# output.net
KiCad netlist of a schematic drawn in Altium Designer
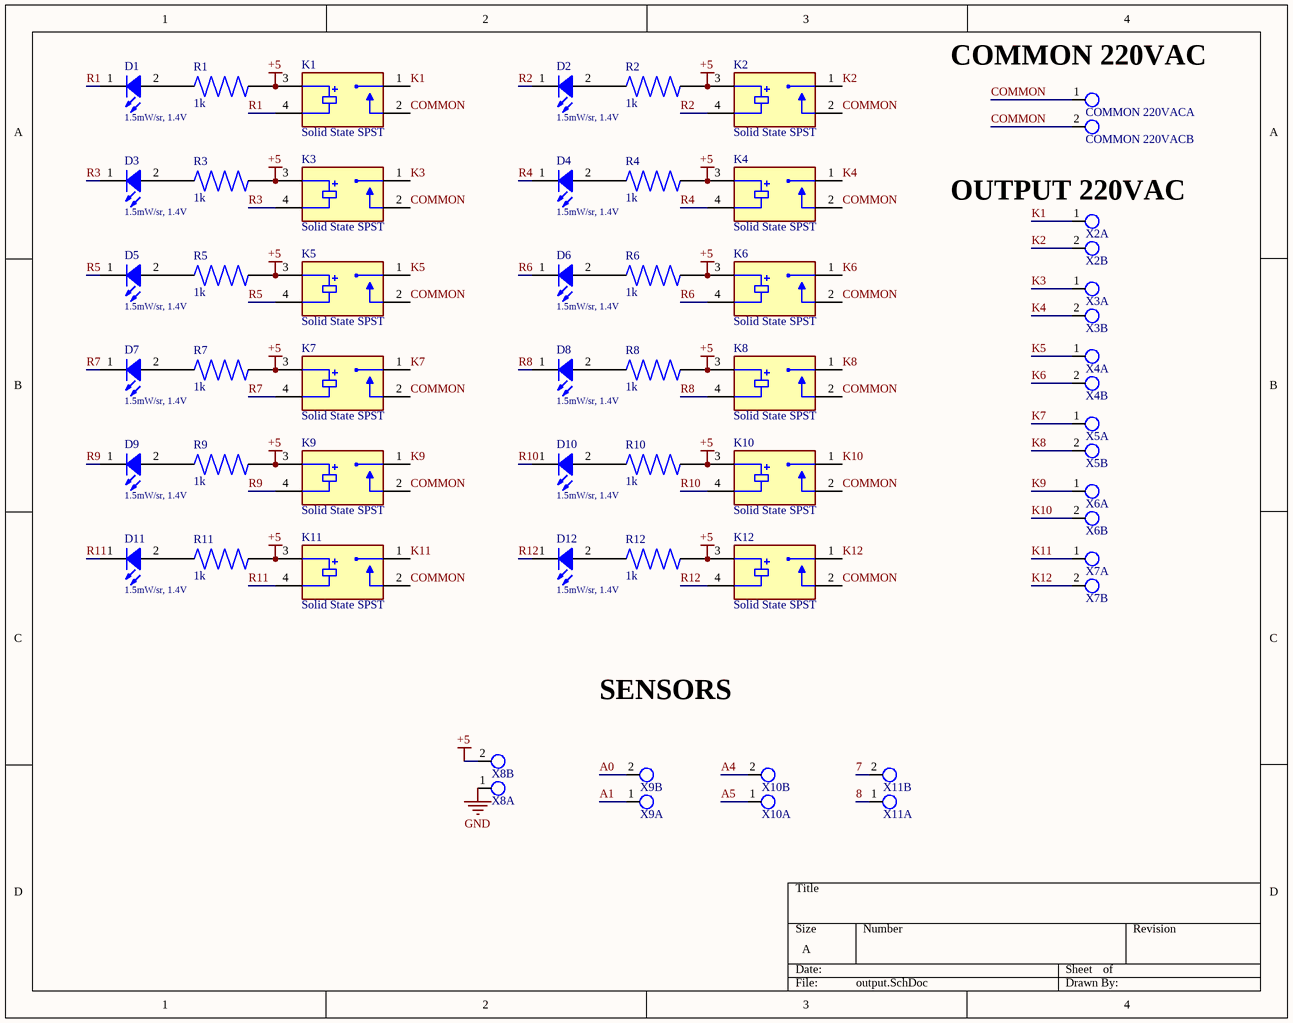
[diagram p0: output.SchDoc]

(export (version "E")
  (design (tool "Eeschema 10.0.6"))
  (components
    (comp (ref "COMMON 220VAC")
      (value "AK300/2")
      (footprint "AK300/2")
      (fields (field (name "MP") "AK300/3") (field (name "MF") "Altech"))
      (libsource (lib "") (part "AK300/2_2"))
    )
    (comp (ref "D1")
      (value "1.5mW/sr, 1.4V")
      (footprint "0805_L2W1.3H0.8")
      (description "WL-SICW SMT Chip LED Infrared Waterclear, size 0805, 1.5mW/sr, 1.4V")
      (fields
        (field (name "MANUFACTURER PART NUMBER") "15408085BA400")
        (field (name "MANUFACTURER") "Wurth Elektronik")
      )
      (libsource (lib "input") (part "0805 Led"))
    )
    (comp (ref "D2")
      (value "1.5mW/sr, 1.4V")
      (footprint "0805_L2W1.3H0.8")
      (description "WL-SICW SMT Chip LED Infrared Waterclear, size 0805, 1.5mW/sr, 1.4V")
      (fields
        (field (name "MANUFACTURER PART NUMBER") "15408085BA400")
        (field (name "MANUFACTURER") "Wurth Elektronik")
      )
      (libsource (lib "input") (part "0805 Led"))
    )
    (comp (ref "D3")
      (value "1.5mW/sr, 1.4V")
      (footprint "0805_L2W1.3H0.8")
      (description "WL-SICW SMT Chip LED Infrared Waterclear, size 0805, 1.5mW/sr, 1.4V")
      (fields
        (field (name "MANUFACTURER PART NUMBER") "15408085BA400")
        (field (name "MANUFACTURER") "Wurth Elektronik")
      )
      (libsource (lib "input") (part "0805 Led"))
    )
    (comp (ref "D4")
      (value "1.5mW/sr, 1.4V")
      (footprint "0805_L2W1.3H0.8")
      (description "WL-SICW SMT Chip LED Infrared Waterclear, size 0805, 1.5mW/sr, 1.4V")
      (fields
        (field (name "MANUFACTURER PART NUMBER") "15408085BA400")
        (field (name "MANUFACTURER") "Wurth Elektronik")
      )
      (libsource (lib "input") (part "0805 Led"))
    )
    (comp (ref "D5")
      (value "1.5mW/sr, 1.4V")
      (footprint "0805_L2W1.3H0.8")
      (description "WL-SICW SMT Chip LED Infrared Waterclear, size 0805, 1.5mW/sr, 1.4V")
      (fields
        (field (name "MANUFACTURER PART NUMBER") "15408085BA400")
        (field (name "MANUFACTURER") "Wurth Elektronik")
      )
      (libsource (lib "input") (part "0805 Led"))
    )
    (comp (ref "D6")
      (value "1.5mW/sr, 1.4V")
      (footprint "0805_L2W1.3H0.8")
      (description "WL-SICW SMT Chip LED Infrared Waterclear, size 0805, 1.5mW/sr, 1.4V")
      (fields
        (field (name "MANUFACTURER PART NUMBER") "15408085BA400")
        (field (name "MANUFACTURER") "Wurth Elektronik")
      )
      (libsource (lib "input") (part "0805 Led"))
    )
    (comp (ref "D7")
      (value "1.5mW/sr, 1.4V")
      (footprint "0805_L2W1.3H0.8")
      (description "WL-SICW SMT Chip LED Infrared Waterclear, size 0805, 1.5mW/sr, 1.4V")
      (fields
        (field (name "MANUFACTURER PART NUMBER") "15408085BA400")
        (field (name "MANUFACTURER") "Wurth Elektronik")
      )
      (libsource (lib "input") (part "0805 Led"))
    )
    (comp (ref "D8")
      (value "1.5mW/sr, 1.4V")
      (footprint "0805_L2W1.3H0.8")
      (description "WL-SICW SMT Chip LED Infrared Waterclear, size 0805, 1.5mW/sr, 1.4V")
      (fields
        (field (name "MANUFACTURER PART NUMBER") "15408085BA400")
        (field (name "MANUFACTURER") "Wurth Elektronik")
      )
      (libsource (lib "input") (part "0805 Led"))
    )
    (comp (ref "D9")
      (value "1.5mW/sr, 1.4V")
      (footprint "0805_L2W1.3H0.8")
      (description "WL-SICW SMT Chip LED Infrared Waterclear, size 0805, 1.5mW/sr, 1.4V")
      (fields
        (field (name "MANUFACTURER PART NUMBER") "15408085BA400")
        (field (name "MANUFACTURER") "Wurth Elektronik")
      )
      (libsource (lib "input") (part "0805 Led"))
    )
    (comp (ref "D10")
      (value "1.5mW/sr, 1.4V")
      (footprint "0805_L2W1.3H0.8")
      (description "WL-SICW SMT Chip LED Infrared Waterclear, size 0805, 1.5mW/sr, 1.4V")
      (fields
        (field (name "MANUFACTURER PART NUMBER") "15408085BA400")
        (field (name "MANUFACTURER") "Wurth Elektronik")
      )
      (libsource (lib "input") (part "0805 Led"))
    )
    (comp (ref "D11")
      (value "1.5mW/sr, 1.4V")
      (footprint "0805_L2W1.3H0.8")
      (description "WL-SICW SMT Chip LED Infrared Waterclear, size 0805, 1.5mW/sr, 1.4V")
      (fields
        (field (name "MANUFACTURER PART NUMBER") "15408085BA400")
        (field (name "MANUFACTURER") "Wurth Elektronik")
      )
      (libsource (lib "input") (part "0805 Led"))
    )
    (comp (ref "D12")
      (value "1.5mW/sr, 1.4V")
      (footprint "0805_L2W1.3H0.8")
      (description "WL-SICW SMT Chip LED Infrared Waterclear, size 0805, 1.5mW/sr, 1.4V")
      (fields
        (field (name "MANUFACTURER PART NUMBER") "15408085BA400")
        (field (name "MANUFACTURER") "Wurth Elektronik")
      )
      (libsource (lib "input") (part "0805 Led"))
    )
    (comp (ref "K1")
      (value "Solid State SPST")
      (footprint "Solid State SPST")
      (description "Solid State SPST-NO (1 Form A) 4-SIP")
      (fields (field (name "MF") "Omron Automation") (field (name "MP") "G3MB-202P DC5"))
      (libsource (lib "control") (part "Solid State SPST"))
    )
    (comp (ref "K2")
      (value "Solid State SPST")
      (footprint "Solid State SPST")
      (description "Solid State SPST-NO (1 Form A) 4-SIP")
      (fields (field (name "MF") "Omron Automation") (field (name "MP") "G3MB-202P DC5"))
      (libsource (lib "control") (part "Solid State SPST"))
    )
    (comp (ref "K3")
      (value "Solid State SPST")
      (footprint "Solid State SPST")
      (description "Solid State SPST-NO (1 Form A) 4-SIP")
      (fields (field (name "MF") "Omron Automation") (field (name "MP") "G3MB-202P DC5"))
      (libsource (lib "control") (part "Solid State SPST"))
    )
    (comp (ref "K4")
      (value "Solid State SPST")
      (footprint "Solid State SPST")
      (description "Solid State SPST-NO (1 Form A) 4-SIP")
      (fields (field (name "MF") "Omron Automation") (field (name "MP") "G3MB-202P DC5"))
      (libsource (lib "control") (part "Solid State SPST"))
    )
    (comp (ref "K5")
      (value "Solid State SPST")
      (footprint "Solid State SPST")
      (description "Solid State SPST-NO (1 Form A) 4-SIP")
      (fields (field (name "MF") "Omron Automation") (field (name "MP") "G3MB-202P DC5"))
      (libsource (lib "control") (part "Solid State SPST"))
    )
    (comp (ref "K6")
      (value "Solid State SPST")
      (footprint "Solid State SPST")
      (description "Solid State SPST-NO (1 Form A) 4-SIP")
      (fields (field (name "MF") "Omron Automation") (field (name "MP") "G3MB-202P DC5"))
      (libsource (lib "control") (part "Solid State SPST"))
    )
    (comp (ref "K7")
      (value "Solid State SPST")
      (footprint "Solid State SPST")
      (description "Solid State SPST-NO (1 Form A) 4-SIP")
      (fields (field (name "MF") "Omron Automation") (field (name "MP") "G3MB-202P DC5"))
      (libsource (lib "control") (part "Solid State SPST"))
    )
    (comp (ref "K8")
      (value "Solid State SPST")
      (footprint "Solid State SPST")
      (description "Solid State SPST-NO (1 Form A) 4-SIP")
      (fields (field (name "MF") "Omron Automation") (field (name "MP") "G3MB-202P DC5"))
      (libsource (lib "control") (part "Solid State SPST"))
    )
    (comp (ref "K9")
      (value "Solid State SPST")
      (footprint "Solid State SPST")
      (description "Solid State SPST-NO (1 Form A) 4-SIP")
      (fields (field (name "MF") "Omron Automation") (field (name "MP") "G3MB-202P DC5"))
      (libsource (lib "control") (part "Solid State SPST"))
    )
    (comp (ref "K10")
      (value "Solid State SPST")
      (footprint "Solid State SPST")
      (description "Solid State SPST-NO (1 Form A) 4-SIP")
      (fields (field (name "MF") "Omron Automation") (field (name "MP") "G3MB-202P DC5"))
      (libsource (lib "control") (part "Solid State SPST"))
    )
    (comp (ref "K11")
      (value "Solid State SPST")
      (footprint "Solid State SPST")
      (description "Solid State SPST-NO (1 Form A) 4-SIP")
      (fields (field (name "MF") "Omron Automation") (field (name "MP") "G3MB-202P DC5"))
      (libsource (lib "control") (part "Solid State SPST"))
    )
    (comp (ref "K12")
      (value "Solid State SPST")
      (footprint "Solid State SPST")
      (description "Solid State SPST-NO (1 Form A) 4-SIP")
      (fields (field (name "MF") "Omron Automation") (field (name "MP") "G3MB-202P DC5"))
      (libsource (lib "control") (part "Solid State SPST"))
    )
    (comp (ref "R1")
      (value "1k")
      (footprint "1206")
      (description "Res 1206 10 Ohm 5% 1/8W Â±500ppm/Â°C Molded SMD SMD T/R")
      (fields (field (name "TOLERANCE") "5%") (field (name "MP") "FCR1206J10R"))
      (libsource (lib "input") (part "1206 Res"))
    )
    (comp (ref "R2")
      (value "1k")
      (footprint "1206")
      (description "Res 1206 10 Ohm 5% 1/8W Â±500ppm/Â°C Molded SMD SMD T/R")
      (fields (field (name "TOLERANCE") "5%") (field (name "MP") "FCR1206J10R"))
      (libsource (lib "input") (part "1206 Res"))
    )
    (comp (ref "R3")
      (value "1k")
      (footprint "1206")
      (description "Res 1206 10 Ohm 5% 1/8W Â±500ppm/Â°C Molded SMD SMD T/R")
      (fields (field (name "TOLERANCE") "5%") (field (name "MP") "FCR1206J10R"))
      (libsource (lib "input") (part "1206 Res"))
    )
    (comp (ref "R4")
      (value "1k")
      (footprint "1206")
      (description "Res 1206 10 Ohm 5% 1/8W Â±500ppm/Â°C Molded SMD SMD T/R")
      (fields (field (name "TOLERANCE") "5%") (field (name "MP") "FCR1206J10R"))
      (libsource (lib "input") (part "1206 Res"))
    )
    (comp (ref "R5")
      (value "1k")
      (footprint "1206")
      (description "Res 1206 10 Ohm 5% 1/8W Â±500ppm/Â°C Molded SMD SMD T/R")
      (fields (field (name "TOLERANCE") "5%") (field (name "MP") "FCR1206J10R"))
      (libsource (lib "input") (part "1206 Res"))
    )
    (comp (ref "R6")
      (value "1k")
      (footprint "1206")
      (description "Res 1206 10 Ohm 5% 1/8W Â±500ppm/Â°C Molded SMD SMD T/R")
      (fields (field (name "TOLERANCE") "5%") (field (name "MP") "FCR1206J10R"))
      (libsource (lib "input") (part "1206 Res"))
    )
    (comp (ref "R7")
      (value "1k")
      (footprint "1206")
      (description "Res 1206 10 Ohm 5% 1/8W Â±500ppm/Â°C Molded SMD SMD T/R")
      (fields (field (name "TOLERANCE") "5%") (field (name "MP") "FCR1206J10R"))
      (libsource (lib "input") (part "1206 Res"))
    )
    (comp (ref "R8")
      (value "1k")
      (footprint "1206")
      (description "Res 1206 10 Ohm 5% 1/8W Â±500ppm/Â°C Molded SMD SMD T/R")
      (fields (field (name "TOLERANCE") "5%") (field (name "MP") "FCR1206J10R"))
      (libsource (lib "input") (part "1206 Res"))
    )
    (comp (ref "R9")
      (value "1k")
      (footprint "1206")
      (description "Res 1206 10 Ohm 5% 1/8W Â±500ppm/Â°C Molded SMD SMD T/R")
      (fields (field (name "TOLERANCE") "5%") (field (name "MP") "FCR1206J10R"))
      (libsource (lib "input") (part "1206 Res"))
    )
    (comp (ref "R10")
      (value "1k")
      (footprint "1206")
      (description "Res 1206 10 Ohm 5% 1/8W Â±500ppm/Â°C Molded SMD SMD T/R")
      (fields (field (name "TOLERANCE") "5%") (field (name "MP") "FCR1206J10R"))
      (libsource (lib "input") (part "1206 Res"))
    )
    (comp (ref "R11")
      (value "1k")
      (footprint "1206")
      (description "Res 1206 10 Ohm 5% 1/8W Â±500ppm/Â°C Molded SMD SMD T/R")
      (fields (field (name "TOLERANCE") "5%") (field (name "MP") "FCR1206J10R"))
      (libsource (lib "input") (part "1206 Res"))
    )
    (comp (ref "R12")
      (value "1k")
      (footprint "1206")
      (description "Res 1206 10 Ohm 5% 1/8W Â±500ppm/Â°C Molded SMD SMD T/R")
      (fields (field (name "TOLERANCE") "5%") (field (name "MP") "FCR1206J10R"))
      (libsource (lib "input") (part "1206 Res"))
    )
    (comp (ref "X2")
      (value "AK300/2")
      (footprint "AK300/2")
      (fields (field (name "MP") "AK300/3") (field (name "MF") "Altech"))
      (libsource (lib "input") (part "AK300/2"))
    )
    (comp (ref "X3")
      (value "AK300/2")
      (footprint "AK300/2")
      (fields (field (name "MP") "AK300/3") (field (name "MF") "Altech"))
      (libsource (lib "input") (part "AK300/2"))
    )
    (comp (ref "X4")
      (value "AK300/2")
      (footprint "AK300/2")
      (fields (field (name "MP") "AK300/3") (field (name "MF") "Altech"))
      (libsource (lib "input") (part "AK300/2"))
    )
    (comp (ref "X5")
      (value "AK300/2")
      (footprint "AK300/2")
      (fields (field (name "MP") "AK300/3") (field (name "MF") "Altech"))
      (libsource (lib "input") (part "AK300/2"))
    )
    (comp (ref "X6")
      (value "AK300/2")
      (footprint "AK300/2")
      (fields (field (name "MP") "AK300/3") (field (name "MF") "Altech"))
      (libsource (lib "input") (part "AK300/2"))
    )
    (comp (ref "X7")
      (value "AK300/2")
      (footprint "AK300/2")
      (fields (field (name "MP") "AK300/3") (field (name "MF") "Altech"))
      (libsource (lib "input") (part "AK300/2"))
    )
    (comp (ref "X8")
      (value "AK300/2")
      (footprint "AK300/2")
      (fields (field (name "MP") "AK300/3") (field (name "MF") "Altech"))
      (libsource (lib "") (part "AK300/2_2"))
    )
    (comp (ref "X9")
      (value "AK300/2")
      (footprint "AK300/2")
      (fields (field (name "MP") "AK300/3") (field (name "MF") "Altech"))
      (libsource (lib "") (part "AK300/2_1"))
    )
    (comp (ref "X10")
      (value "AK300/2")
      (footprint "AK300/2")
      (fields (field (name "MP") "AK300/3") (field (name "MF") "Altech"))
      (libsource (lib "") (part "AK300/2_1"))
    )
    (comp (ref "X11")
      (value "AK300/2")
      (footprint "AK300/2")
      (fields (field (name "MP") "AK300/3") (field (name "MF") "Altech"))
      (libsource (lib "") (part "AK300/2_2"))
    )
  )
  (nets
    (net (code "1") (name "+5") (class "Default")
      (node (ref "K1") (pin "3") (pinfunction "3_3") (pintype "passive"))
      (node (ref "K10") (pin "3") (pinfunction "3_3") (pintype "passive"))
      (node (ref "K11") (pin "3") (pinfunction "3_3") (pintype "passive"))
      (node (ref "K12") (pin "3") (pinfunction "3_3") (pintype "passive"))
      (node (ref "K2") (pin "3") (pinfunction "3_3") (pintype "passive"))
      (node (ref "K3") (pin "3") (pinfunction "3_3") (pintype "passive"))
      (node (ref "K4") (pin "3") (pinfunction "3_3") (pintype "passive"))
      (node (ref "K5") (pin "3") (pinfunction "3_3") (pintype "passive"))
      (node (ref "K6") (pin "3") (pinfunction "3_3") (pintype "passive"))
      (node (ref "K7") (pin "3") (pinfunction "3_3") (pintype "passive"))
      (node (ref "K8") (pin "3") (pinfunction "3_3") (pintype "passive"))
      (node (ref "K9") (pin "3") (pinfunction "3_3") (pintype "passive"))
      (node (ref "R1") (pin "2") (pinfunction "2_2") (pintype "passive"))
      (node (ref "R10") (pin "2") (pinfunction "2_2") (pintype "passive"))
      (node (ref "R11") (pin "2") (pinfunction "2_2") (pintype "passive"))
      (node (ref "R12") (pin "2") (pinfunction "2_2") (pintype "passive"))
      (node (ref "R2") (pin "2") (pinfunction "2_2") (pintype "passive"))
      (node (ref "R3") (pin "2") (pinfunction "2_2") (pintype "passive"))
      (node (ref "R4") (pin "2") (pinfunction "2_2") (pintype "passive"))
      (node (ref "R5") (pin "2") (pinfunction "2_2") (pintype "passive"))
      (node (ref "R6") (pin "2") (pinfunction "2_2") (pintype "passive"))
      (node (ref "R7") (pin "2") (pinfunction "2_2") (pintype "passive"))
      (node (ref "R8") (pin "2") (pinfunction "2_2") (pintype "passive"))
      (node (ref "R9") (pin "2") (pinfunction "2_2") (pintype "passive"))
      (node (ref "X8") (pin "2") (pinfunction "KL_2") (pintype "passive"))
    )
    (net (code "2") (name "/7") (class "Default")
      (node (ref "X11") (pin "2") (pinfunction "KL_2") (pintype "passive"))
    )
    (net (code "3") (name "/8") (class "Default")
      (node (ref "X11") (pin "1") (pinfunction "KL_1") (pintype "passive"))
    )
    (net (code "4") (name "/A0") (class "Default")
      (node (ref "X9") (pin "2") (pinfunction "KL_2") (pintype "passive"))
    )
    (net (code "5") (name "/A1") (class "Default")
      (node (ref "X9") (pin "1") (pinfunction "KL_1") (pintype "passive"))
    )
    (net (code "6") (name "/A4") (class "Default")
      (node (ref "X10") (pin "2") (pinfunction "KL_2") (pintype "passive"))
    )
    (net (code "7") (name "/A5") (class "Default")
      (node (ref "X10") (pin "1") (pinfunction "KL_1") (pintype "passive"))
    )
    (net (code "8") (name "/COMMON") (class "Default")
      (node (ref "COMMON 220VAC") (pin "1") (pinfunction "KL_1") (pintype "passive"))
      (node (ref "COMMON 220VAC") (pin "2") (pinfunction "KL_2") (pintype "passive"))
      (node (ref "K1") (pin "2") (pinfunction "2_2") (pintype "passive"))
      (node (ref "K10") (pin "2") (pinfunction "2_2") (pintype "passive"))
      (node (ref "K11") (pin "2") (pinfunction "2_2") (pintype "passive"))
      (node (ref "K12") (pin "2") (pinfunction "2_2") (pintype "passive"))
      (node (ref "K2") (pin "2") (pinfunction "2_2") (pintype "passive"))
      (node (ref "K3") (pin "2") (pinfunction "2_2") (pintype "passive"))
      (node (ref "K4") (pin "2") (pinfunction "2_2") (pintype "passive"))
      (node (ref "K5") (pin "2") (pinfunction "2_2") (pintype "passive"))
      (node (ref "K6") (pin "2") (pinfunction "2_2") (pintype "passive"))
      (node (ref "K7") (pin "2") (pinfunction "2_2") (pintype "passive"))
      (node (ref "K8") (pin "2") (pinfunction "2_2") (pintype "passive"))
      (node (ref "K9") (pin "2") (pinfunction "2_2") (pintype "passive"))
    )
    (net (code "9") (name "/K1") (class "Default")
      (node (ref "K1") (pin "1") (pinfunction "1_1") (pintype "passive"))
      (node (ref "X2") (pin "1") (pinfunction "KL_1") (pintype "passive"))
    )
    (net (code "10") (name "/K2") (class "Default")
      (node (ref "K2") (pin "1") (pinfunction "1_1") (pintype "passive"))
      (node (ref "X2") (pin "2") (pinfunction "KL_2") (pintype "passive"))
    )
    (net (code "11") (name "/K3") (class "Default")
      (node (ref "K3") (pin "1") (pinfunction "1_1") (pintype "passive"))
      (node (ref "X3") (pin "1") (pinfunction "KL_1") (pintype "passive"))
    )
    (net (code "12") (name "/K4") (class "Default")
      (node (ref "K4") (pin "1") (pinfunction "1_1") (pintype "passive"))
      (node (ref "X3") (pin "2") (pinfunction "KL_2") (pintype "passive"))
    )
    (net (code "13") (name "/K5") (class "Default")
      (node (ref "K5") (pin "1") (pinfunction "1_1") (pintype "passive"))
      (node (ref "X4") (pin "1") (pinfunction "KL_1") (pintype "passive"))
    )
    (net (code "14") (name "/K6") (class "Default")
      (node (ref "K6") (pin "1") (pinfunction "1_1") (pintype "passive"))
      (node (ref "X4") (pin "2") (pinfunction "KL_2") (pintype "passive"))
    )
    (net (code "15") (name "/K7") (class "Default")
      (node (ref "K7") (pin "1") (pinfunction "1_1") (pintype "passive"))
      (node (ref "X5") (pin "1") (pinfunction "KL_1") (pintype "passive"))
    )
    (net (code "16") (name "/K8") (class "Default")
      (node (ref "K8") (pin "1") (pinfunction "1_1") (pintype "passive"))
      (node (ref "X5") (pin "2") (pinfunction "KL_2") (pintype "passive"))
    )
    (net (code "17") (name "/K9") (class "Default")
      (node (ref "K9") (pin "1") (pinfunction "1_1") (pintype "passive"))
      (node (ref "X6") (pin "1") (pinfunction "KL_1") (pintype "passive"))
    )
    (net (code "18") (name "/K10") (class "Default")
      (node (ref "K10") (pin "1") (pinfunction "1_1") (pintype "passive"))
      (node (ref "X6") (pin "2") (pinfunction "KL_2") (pintype "passive"))
    )
    (net (code "19") (name "/K11") (class "Default")
      (node (ref "K11") (pin "1") (pinfunction "1_1") (pintype "passive"))
      (node (ref "X7") (pin "1") (pinfunction "KL_1") (pintype "passive"))
    )
    (net (code "20") (name "/K12") (class "Default")
      (node (ref "K12") (pin "1") (pinfunction "1_1") (pintype "passive"))
      (node (ref "X7") (pin "2") (pinfunction "KL_2") (pintype "passive"))
    )
    (net (code "21") (name "/R1") (class "Default")
      (node (ref "D1") (pin "1") (pinfunction "K_1") (pintype "passive"))
      (node (ref "K1") (pin "4") (pinfunction "4_4") (pintype "passive"))
    )
    (net (code "22") (name "/R2") (class "Default")
      (node (ref "D2") (pin "1") (pinfunction "K_1") (pintype "passive"))
      (node (ref "K2") (pin "4") (pinfunction "4_4") (pintype "passive"))
    )
    (net (code "23") (name "/R3") (class "Default")
      (node (ref "D3") (pin "1") (pinfunction "K_1") (pintype "passive"))
      (node (ref "K3") (pin "4") (pinfunction "4_4") (pintype "passive"))
    )
    (net (code "24") (name "/R4") (class "Default")
      (node (ref "D4") (pin "1") (pinfunction "K_1") (pintype "passive"))
      (node (ref "K4") (pin "4") (pinfunction "4_4") (pintype "passive"))
    )
    (net (code "25") (name "/R5") (class "Default")
      (node (ref "D5") (pin "1") (pinfunction "K_1") (pintype "passive"))
      (node (ref "K5") (pin "4") (pinfunction "4_4") (pintype "passive"))
    )
    (net (code "26") (name "/R6") (class "Default")
      (node (ref "D6") (pin "1") (pinfunction "K_1") (pintype "passive"))
      (node (ref "K6") (pin "4") (pinfunction "4_4") (pintype "passive"))
    )
    (net (code "27") (name "/R7") (class "Default")
      (node (ref "D7") (pin "1") (pinfunction "K_1") (pintype "passive"))
      (node (ref "K7") (pin "4") (pinfunction "4_4") (pintype "passive"))
    )
    (net (code "28") (name "/R8") (class "Default")
      (node (ref "D8") (pin "1") (pinfunction "K_1") (pintype "passive"))
      (node (ref "K8") (pin "4") (pinfunction "4_4") (pintype "passive"))
    )
    (net (code "29") (name "/R9") (class "Default")
      (node (ref "D9") (pin "1") (pinfunction "K_1") (pintype "passive"))
      (node (ref "K9") (pin "4") (pinfunction "4_4") (pintype "passive"))
    )
    (net (code "30") (name "/R10") (class "Default")
      (node (ref "D10") (pin "1") (pinfunction "K_1") (pintype "passive"))
      (node (ref "K10") (pin "4") (pinfunction "4_4") (pintype "passive"))
    )
    (net (code "31") (name "/R11") (class "Default")
      (node (ref "D11") (pin "1") (pinfunction "K_1") (pintype "passive"))
      (node (ref "K11") (pin "4") (pinfunction "4_4") (pintype "passive"))
    )
    (net (code "32") (name "/R12") (class "Default")
      (node (ref "D12") (pin "1") (pinfunction "K_1") (pintype "passive"))
      (node (ref "K12") (pin "4") (pinfunction "4_4") (pintype "passive"))
    )
    (net (code "33") (name "GND") (class "Default")
      (node (ref "X8") (pin "1") (pinfunction "KL_1") (pintype "passive"))
    )
    (net (code "34") (name "Net-(D1-A)") (class "Default")
      (node (ref "D1") (pin "2") (pinfunction "A_2") (pintype "passive"))
      (node (ref "R1") (pin "1") (pinfunction "1_1") (pintype "passive"))
    )
    (net (code "35") (name "Net-(D2-A)") (class "Default")
      (node (ref "D2") (pin "2") (pinfunction "A_2") (pintype "passive"))
      (node (ref "R2") (pin "1") (pinfunction "1_1") (pintype "passive"))
    )
    (net (code "36") (name "Net-(D3-A)") (class "Default")
      (node (ref "D3") (pin "2") (pinfunction "A_2") (pintype "passive"))
      (node (ref "R3") (pin "1") (pinfunction "1_1") (pintype "passive"))
    )
    (net (code "37") (name "Net-(D4-A)") (class "Default")
      (node (ref "D4") (pin "2") (pinfunction "A_2") (pintype "passive"))
      (node (ref "R4") (pin "1") (pinfunction "1_1") (pintype "passive"))
    )
    (net (code "38") (name "Net-(D5-A)") (class "Default")
      (node (ref "D5") (pin "2") (pinfunction "A_2") (pintype "passive"))
      (node (ref "R5") (pin "1") (pinfunction "1_1") (pintype "passive"))
    )
    (net (code "39") (name "Net-(D6-A)") (class "Default")
      (node (ref "D6") (pin "2") (pinfunction "A_2") (pintype "passive"))
      (node (ref "R6") (pin "1") (pinfunction "1_1") (pintype "passive"))
    )
    (net (code "40") (name "Net-(D7-A)") (class "Default")
      (node (ref "D7") (pin "2") (pinfunction "A_2") (pintype "passive"))
      (node (ref "R7") (pin "1") (pinfunction "1_1") (pintype "passive"))
    )
    (net (code "41") (name "Net-(D8-A)") (class "Default")
      (node (ref "D8") (pin "2") (pinfunction "A_2") (pintype "passive"))
      (node (ref "R8") (pin "1") (pinfunction "1_1") (pintype "passive"))
    )
    (net (code "42") (name "Net-(D9-A)") (class "Default")
      (node (ref "D9") (pin "2") (pinfunction "A_2") (pintype "passive"))
      (node (ref "R9") (pin "1") (pinfunction "1_1") (pintype "passive"))
    )
    (net (code "43") (name "Net-(D10-A)") (class "Default")
      (node (ref "D10") (pin "2") (pinfunction "A_2") (pintype "passive"))
      (node (ref "R10") (pin "1") (pinfunction "1_1") (pintype "passive"))
    )
    (net (code "44") (name "Net-(D11-A)") (class "Default")
      (node (ref "D11") (pin "2") (pinfunction "A_2") (pintype "passive"))
      (node (ref "R11") (pin "1") (pinfunction "1_1") (pintype "passive"))
    )
    (net (code "45") (name "Net-(D12-A)") (class "Default")
      (node (ref "D12") (pin "2") (pinfunction "A_2") (pintype "passive"))
      (node (ref "R12") (pin "1") (pinfunction "1_1") (pintype "passive"))
    )
  )
)
